# Motors.net
KiCad netlist of a schematic drawn in Altium Designer
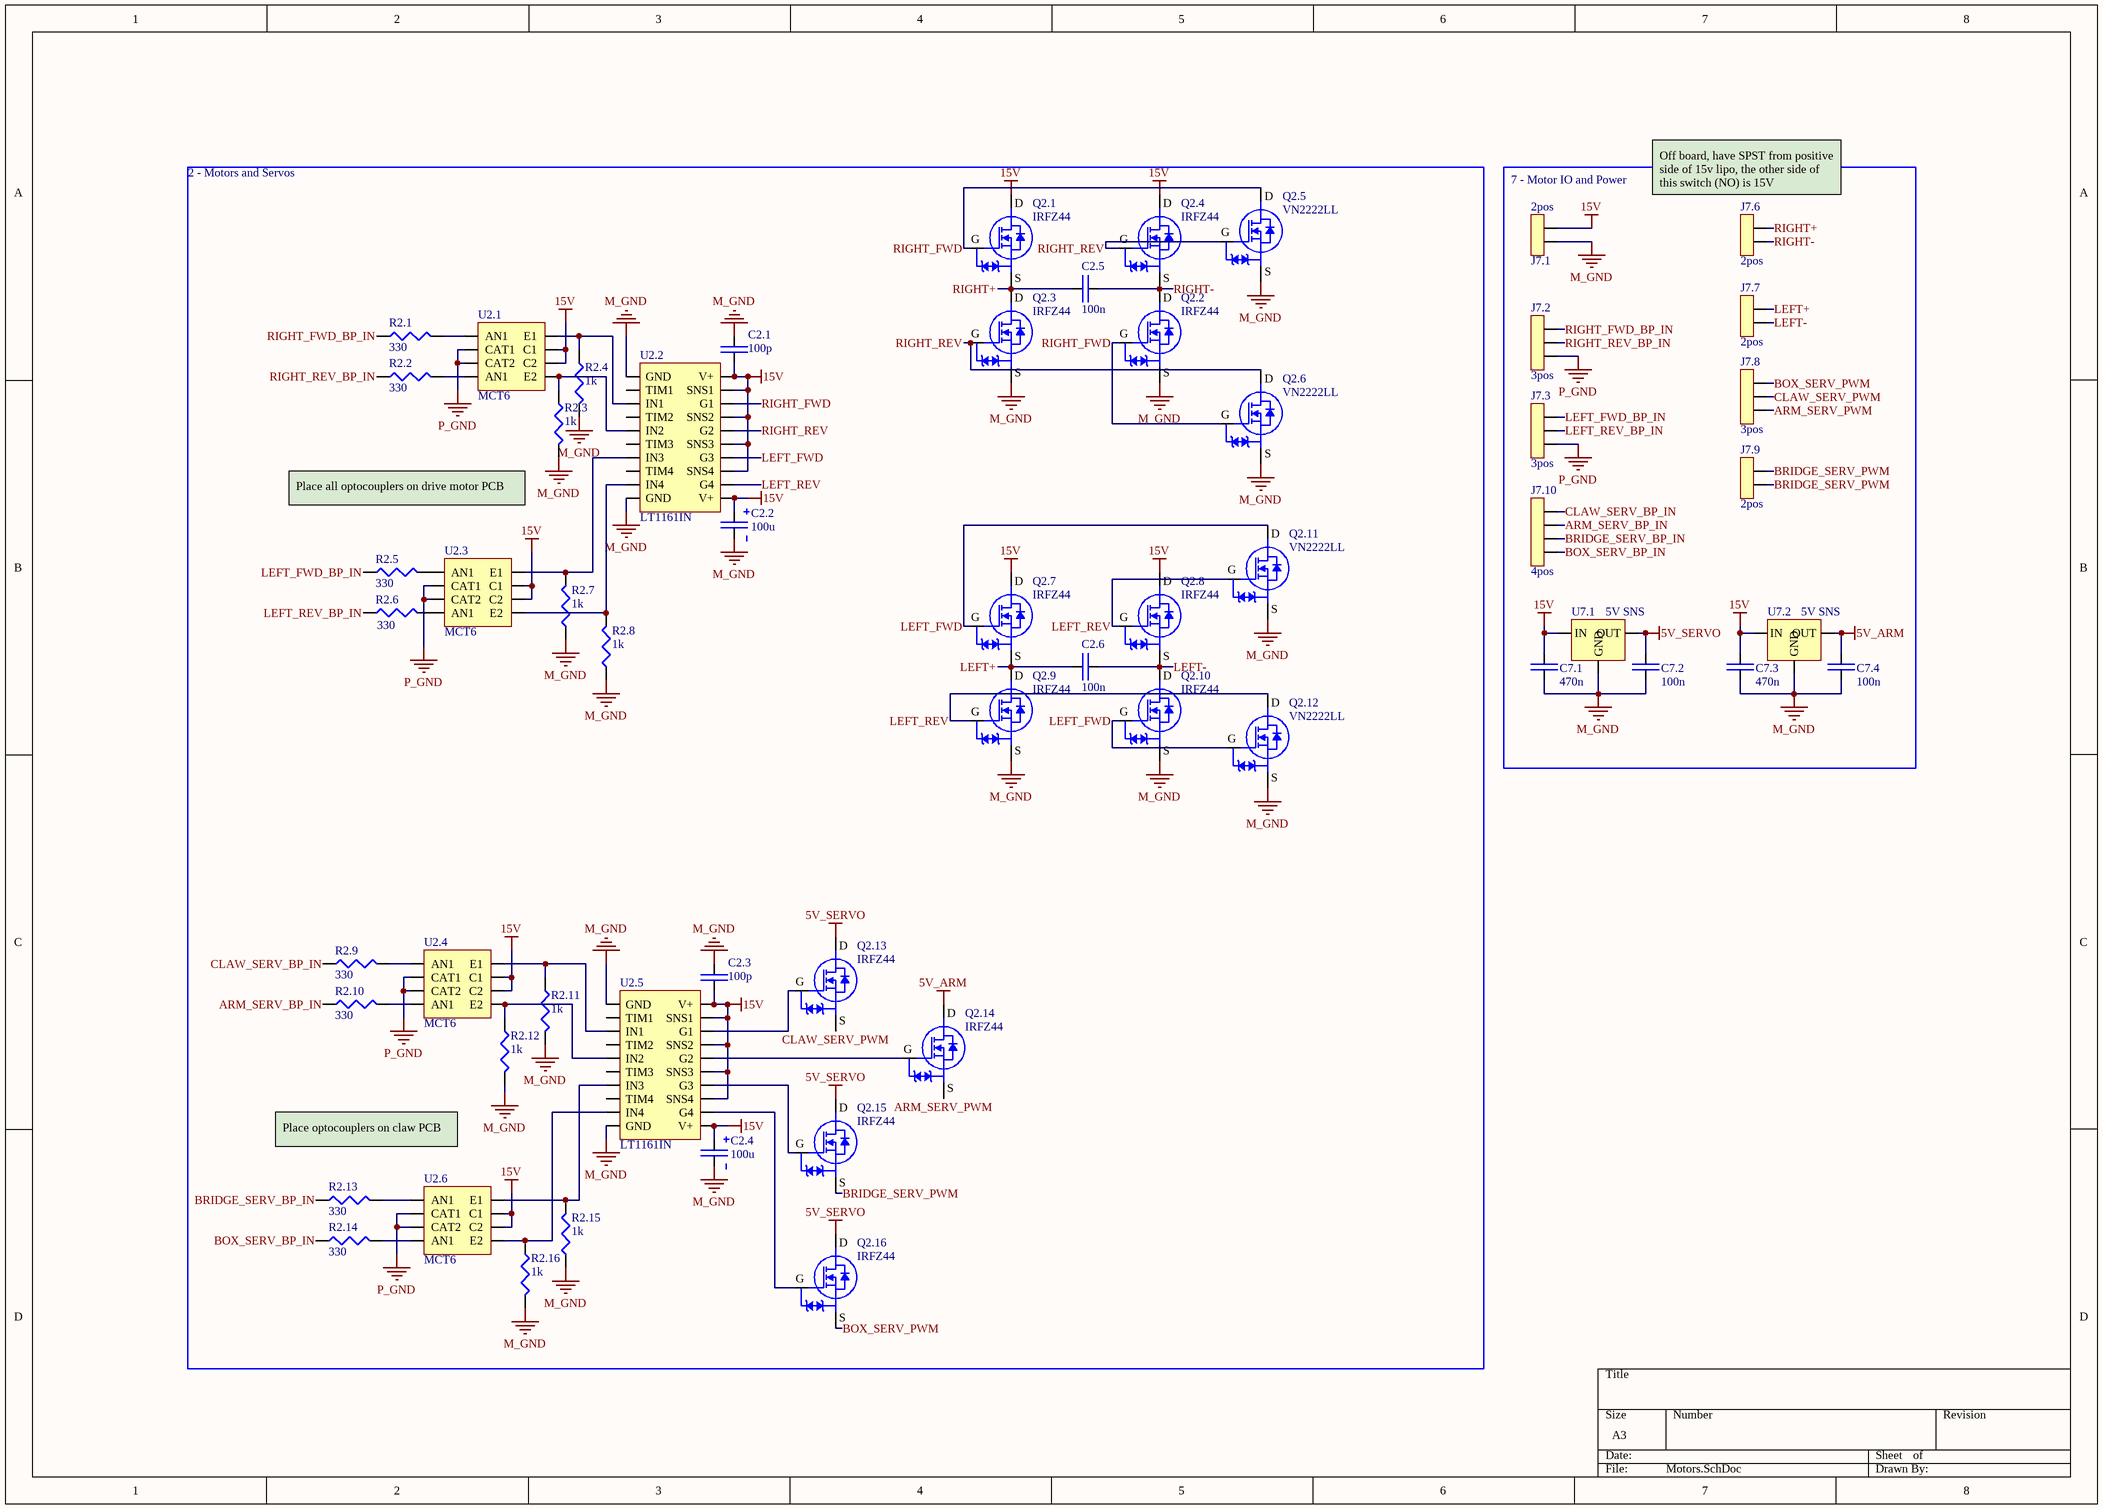
[diagram p0: Motors.SchDoc]

(export (version "E")
  (design (tool "Eeschema 10.0.6"))
  (components
    (comp (ref "C2.1")
      (value "100p")
      (footprint "Non Polarized Cap")
      (libsource (lib "SPICEBot_SchLib") (part "Cap_Generic"))
    )
    (comp (ref "C2.2")
      (value "100u")
      (footprint "Polarized Cap")
      (libsource (lib "SPICEBot_SchLib") (part "Polarized Cap"))
    )
    (comp (ref "C2.3")
      (value "100p")
      (footprint "Non Polarized Cap")
      (libsource (lib "SPICEBot_SchLib") (part "Cap_Generic"))
    )
    (comp (ref "C2.4")
      (value "100u")
      (footprint "Polarized Cap")
      (libsource (lib "SPICEBot_SchLib") (part "Polarized Cap"))
    )
    (comp (ref "C2.5")
      (value "100n")
      (footprint "Non Polarized Cap")
      (libsource (lib "SPICEBot_SchLib") (part "Cap_Generic"))
    )
    (comp (ref "C2.6")
      (value "100n")
      (footprint "Non Polarized Cap")
      (libsource (lib "SPICEBot_SchLib") (part "Cap_Generic"))
    )
    (comp (ref "C7.1")
      (value "470n")
      (footprint "Non Polarized Cap")
      (libsource (lib "SPICEBot_SchLib") (part "Cap_Generic"))
    )
    (comp (ref "C7.2")
      (value "100n")
      (footprint "Non Polarized Cap")
      (libsource (lib "SPICEBot_SchLib") (part "Cap_Generic"))
    )
    (comp (ref "C7.3")
      (value "470n")
      (footprint "Non Polarized Cap")
      (libsource (lib "SPICEBot_SchLib") (part "Cap_Generic"))
    )
    (comp (ref "C7.4")
      (value "100n")
      (footprint "Non Polarized Cap")
      (libsource (lib "SPICEBot_SchLib") (part "Cap_Generic"))
    )
    (comp (ref "J7.1")
      (value "2pos")
      (footprint "2pos JST")
      (description "2pos Conn JST")
      (libsource (lib "SPICEBot_SchLib") (part "2pos Conn"))
    )
    (comp (ref "J7.2")
      (value "3pos")
      (footprint "3pos JST")
      (description "3pos Conn")
      (libsource (lib "SPICEBot_SchLib") (part "3pos Conn"))
    )
    (comp (ref "J7.3")
      (value "3pos")
      (footprint "3pos JST")
      (description "3pos Conn")
      (libsource (lib "SPICEBot_SchLib") (part "3pos Conn"))
    )
    (comp (ref "J7.6")
      (value "2pos")
      (footprint "2pos JST")
      (description "2pos Conn JST")
      (libsource (lib "SPICEBot_SchLib") (part "2pos Conn"))
    )
    (comp (ref "J7.7")
      (value "2pos")
      (footprint "2pos JST")
      (description "2pos Conn JST")
      (libsource (lib "SPICEBot_SchLib") (part "2pos Conn"))
    )
    (comp (ref "J7.8")
      (value "3pos")
      (footprint "3pos JST")
      (description "3pos Conn")
      (libsource (lib "SPICEBot_SchLib") (part "3pos Conn"))
    )
    (comp (ref "J7.9")
      (value "2pos")
      (footprint "2pos JST")
      (description "2pos Conn JST")
      (libsource (lib "SPICEBot_SchLib") (part "2pos Conn"))
    )
    (comp (ref "J7.10")
      (value "4pos")
      (footprint "4Pos JST")
      (description "4pos Conn")
      (libsource (lib "SPICEBot_SchLib") (part "4pos Conn"))
    )
    (comp (ref "Q2.1")
      (value "IRFZ44")
      (footprint "TO220")
      (description "IRFZ44EPBF N-Channel 60 V 48A 110W Through Hole TO-220AB")
      (libsource (lib "SPICEBot_SchLib") (part "IRFZ44 NMOS"))
    )
    (comp (ref "Q2.2")
      (value "IRFZ44")
      (footprint "TO220")
      (description "IRFZ44EPBF N-Channel 60 V 48A 110W Through Hole TO-220AB")
      (libsource (lib "SPICEBot_SchLib") (part "IRFZ44 NMOS"))
    )
    (comp (ref "Q2.3")
      (value "IRFZ44")
      (footprint "TO220")
      (description "IRFZ44EPBF N-Channel 60 V 48A 110W Through Hole TO-220AB")
      (libsource (lib "SPICEBot_SchLib") (part "IRFZ44 NMOS"))
    )
    (comp (ref "Q2.4")
      (value "IRFZ44")
      (footprint "TO220")
      (description "IRFZ44EPBF N-Channel 60 V 48A 110W Through Hole TO-220AB")
      (libsource (lib "SPICEBot_SchLib") (part "IRFZ44 NMOS"))
    )
    (comp (ref "Q2.5")
      (value "VN2222LL")
      (footprint "VN2222LL")
      (description "VN2222LL N-Channel 60 V 150mA 400mW Through Hole TO-92 (TO-226)")
      (libsource (lib "SPICEBot_SchLib") (part "VN2222LL NMOS"))
    )
    (comp (ref "Q2.6")
      (value "VN2222LL")
      (footprint "VN2222LL")
      (description "VN2222LL N-Channel 60 V 150mA 400mW Through Hole TO-92 (TO-226)")
      (libsource (lib "SPICEBot_SchLib") (part "VN2222LL NMOS"))
    )
    (comp (ref "Q2.7")
      (value "IRFZ44")
      (footprint "TO220")
      (description "IRFZ44EPBF N-Channel 60 V 48A 110W Through Hole TO-220AB")
      (libsource (lib "SPICEBot_SchLib") (part "IRFZ44 NMOS"))
    )
    (comp (ref "Q2.8")
      (value "IRFZ44")
      (footprint "TO220")
      (description "IRFZ44EPBF N-Channel 60 V 48A 110W Through Hole TO-220AB")
      (libsource (lib "SPICEBot_SchLib") (part "IRFZ44 NMOS"))
    )
    (comp (ref "Q2.9")
      (value "IRFZ44")
      (footprint "TO220")
      (description "IRFZ44EPBF N-Channel 60 V 48A 110W Through Hole TO-220AB")
      (libsource (lib "SPICEBot_SchLib") (part "IRFZ44 NMOS"))
    )
    (comp (ref "Q2.10")
      (value "IRFZ44")
      (footprint "TO220")
      (description "IRFZ44EPBF N-Channel 60 V 48A 110W Through Hole TO-220AB")
      (libsource (lib "SPICEBot_SchLib") (part "IRFZ44 NMOS"))
    )
    (comp (ref "Q2.11")
      (value "VN2222LL")
      (footprint "VN2222LL")
      (description "VN2222LL N-Channel 60 V 150mA 400mW Through Hole TO-92 (TO-226)")
      (libsource (lib "SPICEBot_SchLib") (part "VN2222LL NMOS"))
    )
    (comp (ref "Q2.12")
      (value "VN2222LL")
      (footprint "VN2222LL")
      (description "VN2222LL N-Channel 60 V 150mA 400mW Through Hole TO-92 (TO-226)")
      (libsource (lib "SPICEBot_SchLib") (part "VN2222LL NMOS"))
    )
    (comp (ref "Q2.13")
      (value "IRFZ44")
      (footprint "TO220")
      (description "IRFZ44EPBF N-Channel 60 V 48A 110W Through Hole TO-220AB")
      (libsource (lib "SPICEBot_SchLib") (part "IRFZ44 NMOS"))
    )
    (comp (ref "Q2.14")
      (value "IRFZ44")
      (footprint "TO220")
      (description "IRFZ44EPBF N-Channel 60 V 48A 110W Through Hole TO-220AB")
      (libsource (lib "SPICEBot_SchLib") (part "IRFZ44 NMOS"))
    )
    (comp (ref "Q2.15")
      (value "IRFZ44")
      (footprint "TO220")
      (description "IRFZ44EPBF N-Channel 60 V 48A 110W Through Hole TO-220AB")
      (libsource (lib "SPICEBot_SchLib") (part "IRFZ44 NMOS"))
    )
    (comp (ref "Q2.16")
      (value "IRFZ44")
      (footprint "TO220")
      (description "IRFZ44EPBF N-Channel 60 V 48A 110W Through Hole TO-220AB")
      (libsource (lib "SPICEBot_SchLib") (part "IRFZ44 NMOS"))
    )
    (comp (ref "R2.1")
      (value "330")
      (footprint "Res_Generic")
      (libsource (lib "SPICEBot_SchLib") (part "Res_Generic"))
    )
    (comp (ref "R2.2")
      (value "330")
      (footprint "Res_Generic")
      (libsource (lib "SPICEBot_SchLib") (part "Res_Generic"))
    )
    (comp (ref "R2.3")
      (value "1k")
      (footprint "Res_Generic")
      (libsource (lib "SPICEBot_SchLib") (part "Res_Generic"))
    )
    (comp (ref "R2.4")
      (value "1k")
      (footprint "Res_Generic")
      (libsource (lib "SPICEBot_SchLib") (part "Res_Generic"))
    )
    (comp (ref "R2.5")
      (value "330")
      (footprint "Res_Generic")
      (libsource (lib "SPICEBot_SchLib") (part "Res_Generic"))
    )
    (comp (ref "R2.6")
      (value "330")
      (footprint "Res_Generic")
      (libsource (lib "SPICEBot_SchLib") (part "Res_Generic"))
    )
    (comp (ref "R2.7")
      (value "1k")
      (footprint "Res_Generic")
      (libsource (lib "SPICEBot_SchLib") (part "Res_Generic"))
    )
    (comp (ref "R2.8")
      (value "1k")
      (footprint "Res_Generic")
      (libsource (lib "SPICEBot_SchLib") (part "Res_Generic"))
    )
    (comp (ref "R2.9")
      (value "330")
      (footprint "Res_Generic")
      (libsource (lib "SPICEBot_SchLib") (part "Res_Generic"))
    )
    (comp (ref "R2.10")
      (value "330")
      (footprint "Res_Generic")
      (libsource (lib "SPICEBot_SchLib") (part "Res_Generic"))
    )
    (comp (ref "R2.11")
      (value "1k")
      (footprint "Res_Generic")
      (libsource (lib "SPICEBot_SchLib") (part "Res_Generic"))
    )
    (comp (ref "R2.12")
      (value "1k")
      (footprint "Res_Generic")
      (libsource (lib "SPICEBot_SchLib") (part "Res_Generic"))
    )
    (comp (ref "R2.13")
      (value "330")
      (footprint "Res_Generic")
      (libsource (lib "SPICEBot_SchLib") (part "Res_Generic"))
    )
    (comp (ref "R2.14")
      (value "330")
      (footprint "Res_Generic")
      (libsource (lib "SPICEBot_SchLib") (part "Res_Generic"))
    )
    (comp (ref "R2.15")
      (value "1k")
      (footprint "Res_Generic")
      (libsource (lib "SPICEBot_SchLib") (part "Res_Generic"))
    )
    (comp (ref "R2.16")
      (value "1k")
      (footprint "Res_Generic")
      (libsource (lib "SPICEBot_SchLib") (part "Res_Generic"))
    )
    (comp (ref "U2.1")
      (value "MCT6")
      (footprint "DIP8")
      (description "Optoisolator 5.3KV 2CH TRANS 8-DIP")
      (libsource (lib "SPICEBot_SchLib") (part "MCT6 Optocoupler"))
    )
    (comp (ref "U2.2")
      (value "LT1161IN")
      (footprint "DIP20")
      (description "LT1161IN High-Side Gate Driver IC Non-Inverting 20-PDIP")
      (libsource (lib "SPICEBot_SchLib") (part "LT1161IN Gate Driver"))
    )
    (comp (ref "U2.3")
      (value "MCT6")
      (footprint "DIP8")
      (description "Optoisolator 5.3KV 2CH TRANS 8-DIP")
      (libsource (lib "SPICEBot_SchLib") (part "MCT6 Optocoupler"))
    )
    (comp (ref "U2.4")
      (value "MCT6")
      (footprint "DIP8")
      (description "Optoisolator 5.3KV 2CH TRANS 8-DIP")
      (libsource (lib "SPICEBot_SchLib") (part "MCT6 Optocoupler"))
    )
    (comp (ref "U2.5")
      (value "LT1161IN")
      (footprint "DIP20")
      (description "LT1161IN High-Side Gate Driver IC Non-Inverting 20-PDIP")
      (libsource (lib "SPICEBot_SchLib") (part "LT1161IN Gate Driver"))
    )
    (comp (ref "U2.6")
      (value "MCT6")
      (footprint "DIP8")
      (description "Optoisolator 5.3KV 2CH TRANS 8-DIP")
      (libsource (lib "SPICEBot_SchLib") (part "MCT6 Optocoupler"))
    )
    (comp (ref "U7.1")
      (value "5V SNS")
      (footprint "TO220")
      (description "UA7805 IC REG LINEAR 5V 1.5A TO220-3")
      (libsource (lib "SPICEBot_SchLib") (part "UA7805 5V Reg"))
    )
    (comp (ref "U7.2")
      (value "5V SNS")
      (footprint "TO220")
      (description "UA7805 IC REG LINEAR 5V 1.5A TO220-3")
      (libsource (lib "SPICEBot_SchLib") (part "UA7805 5V Reg"))
    )
  )
  (nets
    (net (code "1") (name "/ARM_SERV_BP_IN") (class "Default")
      (node (ref "J7.10") (pin "3") (pinfunction "3_3") (pintype "passive"))
      (node (ref "R2.10") (pin "1") (pinfunction "1_1") (pintype "passive"))
    )
    (net (code "2") (name "/ARM_SERV_PWM") (class "Default")
      (node (ref "J7.8") (pin "1") (pinfunction "1_1") (pintype "passive"))
      (node (ref "Q2.14") (pin "2") (pinfunction "S_2") (pintype "passive"))
    )
    (net (code "3") (name "/BOX_SERV_BP_IN") (class "Default")
      (node (ref "J7.10") (pin "1") (pinfunction "1_1") (pintype "passive"))
      (node (ref "R2.14") (pin "1") (pinfunction "1_1") (pintype "passive"))
    )
    (net (code "4") (name "/BOX_SERV_PWM") (class "Default")
      (node (ref "J7.8") (pin "3") (pinfunction "3_3") (pintype "passive"))
      (node (ref "Q2.16") (pin "2") (pinfunction "S_2") (pintype "passive"))
    )
    (net (code "5") (name "/BRIDGE_SERV_BP_IN") (class "Default")
      (node (ref "J7.10") (pin "2") (pinfunction "2_2") (pintype "passive"))
      (node (ref "R2.13") (pin "1") (pinfunction "1_1") (pintype "passive"))
    )
    (net (code "6") (name "/BRIDGE_SERV_PWM") (class "Default")
      (node (ref "J7.9") (pin "1") (pinfunction "1_1") (pintype "passive"))
      (node (ref "J7.9") (pin "2") (pinfunction "2_2") (pintype "passive"))
      (node (ref "Q2.15") (pin "2") (pinfunction "S_2") (pintype "passive"))
    )
    (net (code "7") (name "/CLAW_SERV_BP_IN") (class "Default")
      (node (ref "J7.10") (pin "4") (pinfunction "4_4") (pintype "passive"))
      (node (ref "R2.9") (pin "1") (pinfunction "1_1") (pintype "passive"))
    )
    (net (code "8") (name "/CLAW_SERV_PWM") (class "Default")
      (node (ref "J7.8") (pin "2") (pinfunction "2_2") (pintype "passive"))
      (node (ref "Q2.13") (pin "2") (pinfunction "S_2") (pintype "passive"))
    )
    (net (code "9") (name "/LEFT+") (class "Default")
      (node (ref "C2.6") (pin "1") (pinfunction "1_1") (pintype "passive"))
      (node (ref "J7.7") (pin "2") (pinfunction "2_2") (pintype "passive"))
      (node (ref "Q2.7") (pin "2") (pinfunction "S_2") (pintype "passive"))
      (node (ref "Q2.9") (pin "3") (pinfunction "D_3") (pintype "passive"))
    )
    (net (code "10") (name "/LEFT-") (class "Default")
      (node (ref "C2.6") (pin "2") (pinfunction "2_2") (pintype "passive"))
      (node (ref "J7.7") (pin "1") (pinfunction "1_1") (pintype "passive"))
      (node (ref "Q2.10") (pin "3") (pinfunction "D_3") (pintype "passive"))
      (node (ref "Q2.8") (pin "2") (pinfunction "S_2") (pintype "passive"))
    )
    (net (code "11") (name "/LEFT_FWD") (class "Default")
      (node (ref "Q2.10") (pin "1") (pinfunction "G_1") (pintype "passive"))
      (node (ref "Q2.11") (pin "3") (pinfunction "D_3") (pintype "passive"))
      (node (ref "Q2.12") (pin "1") (pinfunction "G_1") (pintype "passive"))
      (node (ref "Q2.7") (pin "1") (pinfunction "G_1") (pintype "passive"))
      (node (ref "U2.2") (pin "14") (pinfunction "G3_14") (pintype "passive"))
    )
    (net (code "12") (name "/LEFT_FWD_BP_IN") (class "Default")
      (node (ref "J7.3") (pin "3") (pinfunction "3_3") (pintype "passive"))
      (node (ref "R2.5") (pin "1") (pinfunction "1_1") (pintype "passive"))
    )
    (net (code "13") (name "/LEFT_REV") (class "Default")
      (node (ref "Q2.11") (pin "1") (pinfunction "G_1") (pintype "passive"))
      (node (ref "Q2.12") (pin "3") (pinfunction "D_3") (pintype "passive"))
      (node (ref "Q2.8") (pin "1") (pinfunction "G_1") (pintype "passive"))
      (node (ref "Q2.9") (pin "1") (pinfunction "G_1") (pintype "passive"))
      (node (ref "U2.2") (pin "12") (pinfunction "G4_12") (pintype "passive"))
    )
    (net (code "14") (name "/LEFT_REV_BP_IN") (class "Default")
      (node (ref "J7.3") (pin "2") (pinfunction "2_2") (pintype "passive"))
      (node (ref "R2.6") (pin "1") (pinfunction "1_1") (pintype "passive"))
    )
    (net (code "15") (name "/RIGHT+") (class "Default")
      (node (ref "C2.5") (pin "1") (pinfunction "1_1") (pintype "passive"))
      (node (ref "J7.6") (pin "2") (pinfunction "2_2") (pintype "passive"))
      (node (ref "Q2.1") (pin "2") (pinfunction "S_2") (pintype "passive"))
      (node (ref "Q2.3") (pin "3") (pinfunction "D_3") (pintype "passive"))
    )
    (net (code "16") (name "/RIGHT-") (class "Default")
      (node (ref "C2.5") (pin "2") (pinfunction "2_2") (pintype "passive"))
      (node (ref "J7.6") (pin "1") (pinfunction "1_1") (pintype "passive"))
      (node (ref "Q2.2") (pin "3") (pinfunction "D_3") (pintype "passive"))
      (node (ref "Q2.4") (pin "2") (pinfunction "S_2") (pintype "passive"))
    )
    (net (code "17") (name "/RIGHT_FWD") (class "Default")
      (node (ref "Q2.1") (pin "1") (pinfunction "G_1") (pintype "passive"))
      (node (ref "Q2.2") (pin "1") (pinfunction "G_1") (pintype "passive"))
      (node (ref "Q2.5") (pin "3") (pinfunction "D_3") (pintype "passive"))
      (node (ref "Q2.6") (pin "1") (pinfunction "G_1") (pintype "passive"))
      (node (ref "U2.2") (pin "18") (pinfunction "G1_18") (pintype "passive"))
    )
    (net (code "18") (name "/RIGHT_FWD_BP_IN") (class "Default")
      (node (ref "J7.2") (pin "3") (pinfunction "3_3") (pintype "passive"))
      (node (ref "R2.1") (pin "1") (pinfunction "1_1") (pintype "passive"))
    )
    (net (code "19") (name "/RIGHT_REV") (class "Default")
      (node (ref "Q2.3") (pin "1") (pinfunction "G_1") (pintype "passive"))
      (node (ref "Q2.4") (pin "1") (pinfunction "G_1") (pintype "passive"))
      (node (ref "Q2.5") (pin "1") (pinfunction "G_1") (pintype "passive"))
      (node (ref "Q2.6") (pin "3") (pinfunction "D_3") (pintype "passive"))
      (node (ref "U2.2") (pin "16") (pinfunction "G2_16") (pintype "passive"))
    )
    (net (code "20") (name "/RIGHT_REV_BP_IN") (class "Default")
      (node (ref "J7.2") (pin "2") (pinfunction "2_2") (pintype "passive"))
      (node (ref "R2.2") (pin "1") (pinfunction "1_1") (pintype "passive"))
    )
    (net (code "21") (name "5V_ARM") (class "Default")
      (node (ref "C7.4") (pin "2") (pinfunction "2_2") (pintype "passive"))
      (node (ref "Q2.14") (pin "3") (pinfunction "D_3") (pintype "passive"))
      (node (ref "U7.2") (pin "3") (pinfunction "OUT_3") (pintype "passive"))
    )
    (net (code "22") (name "5V_SERVO") (class "Default")
      (node (ref "C7.2") (pin "2") (pinfunction "2_2") (pintype "passive"))
      (node (ref "Q2.13") (pin "3") (pinfunction "D_3") (pintype "passive"))
      (node (ref "Q2.15") (pin "3") (pinfunction "D_3") (pintype "passive"))
      (node (ref "Q2.16") (pin "3") (pinfunction "D_3") (pintype "passive"))
      (node (ref "U7.1") (pin "3") (pinfunction "OUT_3") (pintype "passive"))
    )
    (net (code "23") (name "15V") (class "Default")
      (node (ref "C2.1") (pin "1") (pinfunction "1_1") (pintype "passive"))
      (node (ref "C2.2") (pin "1") (pinfunction "1_1") (pintype "passive"))
      (node (ref "C2.3") (pin "1") (pinfunction "1_1") (pintype "passive"))
      (node (ref "C2.4") (pin "1") (pinfunction "1_1") (pintype "passive"))
      (node (ref "C7.1") (pin "2") (pinfunction "2_2") (pintype "passive"))
      (node (ref "C7.3") (pin "2") (pinfunction "2_2") (pintype "passive"))
      (node (ref "J7.1") (pin "2") (pinfunction "2_2") (pintype "passive"))
      (node (ref "Q2.1") (pin "3") (pinfunction "D_3") (pintype "passive"))
      (node (ref "Q2.4") (pin "3") (pinfunction "D_3") (pintype "passive"))
      (node (ref "Q2.7") (pin "3") (pinfunction "D_3") (pintype "passive"))
      (node (ref "Q2.8") (pin "3") (pinfunction "D_3") (pintype "passive"))
      (node (ref "U2.1") (pin "6") (pinfunction "C2_6") (pintype "passive"))
      (node (ref "U2.1") (pin "7") (pinfunction "C1_7") (pintype "passive"))
      (node (ref "U2.2") (pin "11") (pinfunction "V+_11") (pintype "passive"))
      (node (ref "U2.2") (pin "13") (pinfunction "SNS4_13") (pintype "passive"))
      (node (ref "U2.2") (pin "15") (pinfunction "SNS3_15") (pintype "passive"))
      (node (ref "U2.2") (pin "17") (pinfunction "SNS2_17") (pintype "passive"))
      (node (ref "U2.2") (pin "19") (pinfunction "SNS1_19") (pintype "passive"))
      (node (ref "U2.2") (pin "20") (pinfunction "V+_20") (pintype "passive"))
      (node (ref "U2.3") (pin "6") (pinfunction "C2_6") (pintype "passive"))
      (node (ref "U2.3") (pin "7") (pinfunction "C1_7") (pintype "passive"))
      (node (ref "U2.4") (pin "6") (pinfunction "C2_6") (pintype "passive"))
      (node (ref "U2.4") (pin "7") (pinfunction "C1_7") (pintype "passive"))
      (node (ref "U2.5") (pin "11") (pinfunction "V+_11") (pintype "passive"))
      (node (ref "U2.5") (pin "13") (pinfunction "SNS4_13") (pintype "passive"))
      (node (ref "U2.5") (pin "15") (pinfunction "SNS3_15") (pintype "passive"))
      (node (ref "U2.5") (pin "17") (pinfunction "SNS2_17") (pintype "passive"))
      (node (ref "U2.5") (pin "19") (pinfunction "SNS1_19") (pintype "passive"))
      (node (ref "U2.5") (pin "20") (pinfunction "V+_20") (pintype "passive"))
      (node (ref "U2.6") (pin "6") (pinfunction "C2_6") (pintype "passive"))
      (node (ref "U2.6") (pin "7") (pinfunction "C1_7") (pintype "passive"))
      (node (ref "U7.1") (pin "1") (pinfunction "IN_1") (pintype "passive"))
      (node (ref "U7.2") (pin "1") (pinfunction "IN_1") (pintype "passive"))
    )
    (net (code "24") (name "M_GND") (class "Default")
      (node (ref "C2.1") (pin "2") (pinfunction "2_2") (pintype "passive"))
      (node (ref "C2.2") (pin "2") (pinfunction "2_2") (pintype "passive"))
      (node (ref "C2.3") (pin "2") (pinfunction "2_2") (pintype "passive"))
      (node (ref "C2.4") (pin "2") (pinfunction "2_2") (pintype "passive"))
      (node (ref "C7.1") (pin "1") (pinfunction "1_1") (pintype "passive"))
      (node (ref "C7.2") (pin "1") (pinfunction "1_1") (pintype "passive"))
      (node (ref "C7.3") (pin "1") (pinfunction "1_1") (pintype "passive"))
      (node (ref "C7.4") (pin "1") (pinfunction "1_1") (pintype "passive"))
      (node (ref "J7.1") (pin "1") (pinfunction "1_1") (pintype "passive"))
      (node (ref "Q2.10") (pin "2") (pinfunction "S_2") (pintype "passive"))
      (node (ref "Q2.11") (pin "2") (pinfunction "S_2") (pintype "passive"))
      (node (ref "Q2.12") (pin "2") (pinfunction "S_2") (pintype "passive"))
      (node (ref "Q2.2") (pin "2") (pinfunction "S_2") (pintype "passive"))
      (node (ref "Q2.3") (pin "2") (pinfunction "S_2") (pintype "passive"))
      (node (ref "Q2.5") (pin "2") (pinfunction "S_2") (pintype "passive"))
      (node (ref "Q2.6") (pin "2") (pinfunction "S_2") (pintype "passive"))
      (node (ref "Q2.9") (pin "2") (pinfunction "S_2") (pintype "passive"))
      (node (ref "R2.11") (pin "2") (pinfunction "2_2") (pintype "passive"))
      (node (ref "R2.12") (pin "2") (pinfunction "2_2") (pintype "passive"))
      (node (ref "R2.15") (pin "1") (pinfunction "1_1") (pintype "passive"))
      (node (ref "R2.16") (pin "2") (pinfunction "2_2") (pintype "passive"))
      (node (ref "R2.3") (pin "2") (pinfunction "2_2") (pintype "passive"))
      (node (ref "R2.4") (pin "2") (pinfunction "2_2") (pintype "passive"))
      (node (ref "R2.7") (pin "1") (pinfunction "1_1") (pintype "passive"))
      (node (ref "R2.8") (pin "1") (pinfunction "1_1") (pintype "passive"))
      (node (ref "U2.2") (pin "1") (pinfunction "GND_1") (pintype "passive"))
      (node (ref "U2.2") (pin "10") (pinfunction "GND_10") (pintype "passive"))
      (node (ref "U2.5") (pin "1") (pinfunction "GND_1") (pintype "passive"))
      (node (ref "U2.5") (pin "10") (pinfunction "GND_10") (pintype "passive"))
      (node (ref "U7.1") (pin "2") (pinfunction "GND_2") (pintype "passive"))
      (node (ref "U7.2") (pin "2") (pinfunction "GND_2") (pintype "passive"))
    )
    (net (code "25") (name "Net-(Q2.13-G)") (class "Default")
      (node (ref "Q2.13") (pin "1") (pinfunction "G_1") (pintype "passive"))
      (node (ref "U2.5") (pin "18") (pinfunction "G1_18") (pintype "passive"))
    )
    (net (code "26") (name "Net-(Q2.14-G)") (class "Default")
      (node (ref "Q2.14") (pin "1") (pinfunction "G_1") (pintype "passive"))
      (node (ref "U2.5") (pin "16") (pinfunction "G2_16") (pintype "passive"))
    )
    (net (code "27") (name "Net-(Q2.15-G)") (class "Default")
      (node (ref "Q2.15") (pin "1") (pinfunction "G_1") (pintype "passive"))
      (node (ref "U2.5") (pin "14") (pinfunction "G3_14") (pintype "passive"))
    )
    (net (code "28") (name "Net-(Q2.16-G)") (class "Default")
      (node (ref "Q2.16") (pin "1") (pinfunction "G_1") (pintype "passive"))
      (node (ref "U2.5") (pin "12") (pinfunction "G4_12") (pintype "passive"))
    )
    (net (code "29") (name "Net-(R2.1-Pad2)") (class "Default")
      (node (ref "R2.1") (pin "2") (pinfunction "2_2") (pintype "passive"))
      (node (ref "U2.1") (pin "1") (pinfunction "AN1_1") (pintype "passive"))
    )
    (net (code "30") (name "Net-(R2.2-Pad2)") (class "Default")
      (node (ref "R2.2") (pin "2") (pinfunction "2_2") (pintype "passive"))
      (node (ref "U2.1") (pin "4") (pinfunction "AN1_4") (pintype "passive"))
    )
    (net (code "31") (name "Net-(R2.5-Pad2)") (class "Default")
      (node (ref "R2.5") (pin "2") (pinfunction "2_2") (pintype "passive"))
      (node (ref "U2.3") (pin "1") (pinfunction "AN1_1") (pintype "passive"))
    )
    (net (code "32") (name "Net-(R2.6-Pad2)") (class "Default")
      (node (ref "R2.6") (pin "2") (pinfunction "2_2") (pintype "passive"))
      (node (ref "U2.3") (pin "4") (pinfunction "AN1_4") (pintype "passive"))
    )
    (net (code "33") (name "Net-(R2.9-Pad2)") (class "Default")
      (node (ref "R2.9") (pin "2") (pinfunction "2_2") (pintype "passive"))
      (node (ref "U2.4") (pin "1") (pinfunction "AN1_1") (pintype "passive"))
    )
    (net (code "34") (name "Net-(R2.10-Pad2)") (class "Default")
      (node (ref "R2.10") (pin "2") (pinfunction "2_2") (pintype "passive"))
      (node (ref "U2.4") (pin "4") (pinfunction "AN1_4") (pintype "passive"))
    )
    (net (code "35") (name "Net-(R2.13-Pad2)") (class "Default")
      (node (ref "R2.13") (pin "2") (pinfunction "2_2") (pintype "passive"))
      (node (ref "U2.6") (pin "1") (pinfunction "AN1_1") (pintype "passive"))
    )
    (net (code "36") (name "Net-(R2.14-Pad2)") (class "Default")
      (node (ref "R2.14") (pin "2") (pinfunction "2_2") (pintype "passive"))
      (node (ref "U2.6") (pin "4") (pinfunction "AN1_4") (pintype "passive"))
    )
    (net (code "37") (name "Net-(U2.1-E1)") (class "Default")
      (node (ref "R2.4") (pin "1") (pinfunction "1_1") (pintype "passive"))
      (node (ref "U2.1") (pin "8") (pinfunction "E1_8") (pintype "passive"))
      (node (ref "U2.2") (pin "3") (pinfunction "IN1_3") (pintype "passive"))
    )
    (net (code "38") (name "Net-(U2.1-E2)") (class "Default")
      (node (ref "R2.3") (pin "1") (pinfunction "1_1") (pintype "passive"))
      (node (ref "U2.1") (pin "5") (pinfunction "E2_5") (pintype "passive"))
      (node (ref "U2.2") (pin "5") (pinfunction "IN2_5") (pintype "passive"))
    )
    (net (code "39") (name "Net-(U2.2-IN3)") (class "Default")
      (node (ref "R2.7") (pin "2") (pinfunction "2_2") (pintype "passive"))
      (node (ref "U2.2") (pin "7") (pinfunction "IN3_7") (pintype "passive"))
      (node (ref "U2.3") (pin "8") (pinfunction "E1_8") (pintype "passive"))
    )
    (net (code "40") (name "Net-(U2.2-IN4)") (class "Default")
      (node (ref "R2.8") (pin "2") (pinfunction "2_2") (pintype "passive"))
      (node (ref "U2.2") (pin "9") (pinfunction "IN4_9") (pintype "passive"))
      (node (ref "U2.3") (pin "5") (pinfunction "E2_5") (pintype "passive"))
    )
    (net (code "41") (name "Net-(U2.4-E1)") (class "Default")
      (node (ref "R2.11") (pin "1") (pinfunction "1_1") (pintype "passive"))
      (node (ref "U2.4") (pin "8") (pinfunction "E1_8") (pintype "passive"))
      (node (ref "U2.5") (pin "3") (pinfunction "IN1_3") (pintype "passive"))
    )
    (net (code "42") (name "Net-(U2.4-E2)") (class "Default")
      (node (ref "R2.12") (pin "1") (pinfunction "1_1") (pintype "passive"))
      (node (ref "U2.4") (pin "5") (pinfunction "E2_5") (pintype "passive"))
      (node (ref "U2.5") (pin "5") (pinfunction "IN2_5") (pintype "passive"))
    )
    (net (code "43") (name "Net-(U2.5-IN3)") (class "Default")
      (node (ref "R2.15") (pin "2") (pinfunction "2_2") (pintype "passive"))
      (node (ref "U2.5") (pin "7") (pinfunction "IN3_7") (pintype "passive"))
      (node (ref "U2.6") (pin "8") (pinfunction "E1_8") (pintype "passive"))
    )
    (net (code "44") (name "Net-(U2.5-IN4)") (class "Default")
      (node (ref "R2.16") (pin "1") (pinfunction "1_1") (pintype "passive"))
      (node (ref "U2.5") (pin "9") (pinfunction "IN4_9") (pintype "passive"))
      (node (ref "U2.6") (pin "5") (pinfunction "E2_5") (pintype "passive"))
    )
    (net (code "45") (name "P_GND") (class "Default")
      (node (ref "J7.2") (pin "1") (pinfunction "1_1") (pintype "passive"))
      (node (ref "J7.3") (pin "1") (pinfunction "1_1") (pintype "passive"))
      (node (ref "U2.1") (pin "2") (pinfunction "CAT1_2") (pintype "passive"))
      (node (ref "U2.1") (pin "3") (pinfunction "CAT2_3") (pintype "passive"))
      (node (ref "U2.3") (pin "2") (pinfunction "CAT1_2") (pintype "passive"))
      (node (ref "U2.3") (pin "3") (pinfunction "CAT2_3") (pintype "passive"))
      (node (ref "U2.4") (pin "2") (pinfunction "CAT1_2") (pintype "passive"))
      (node (ref "U2.4") (pin "3") (pinfunction "CAT2_3") (pintype "passive"))
      (node (ref "U2.6") (pin "2") (pinfunction "CAT1_2") (pintype "passive"))
      (node (ref "U2.6") (pin "3") (pinfunction "CAT2_3") (pintype "passive"))
    )
    (net (code "46") (name "unconnected-(U2.2-TIM1-Pad2)") (class "Default")
      (node (ref "U2.2") (pin "2") (pinfunction "TIM1_2") (pintype "passive"))
    )
    (net (code "47") (name "unconnected-(U2.2-TIM2-Pad4)") (class "Default")
      (node (ref "U2.2") (pin "4") (pinfunction "TIM2_4") (pintype "passive"))
    )
    (net (code "48") (name "unconnected-(U2.2-TIM3-Pad6)") (class "Default")
      (node (ref "U2.2") (pin "6") (pinfunction "TIM3_6") (pintype "passive"))
    )
    (net (code "49") (name "unconnected-(U2.2-TIM4-Pad8)") (class "Default")
      (node (ref "U2.2") (pin "8") (pinfunction "TIM4_8") (pintype "passive"))
    )
    (net (code "50") (name "unconnected-(U2.5-TIM1-Pad2)") (class "Default")
      (node (ref "U2.5") (pin "2") (pinfunction "TIM1_2") (pintype "passive"))
    )
    (net (code "51") (name "unconnected-(U2.5-TIM2-Pad4)") (class "Default")
      (node (ref "U2.5") (pin "4") (pinfunction "TIM2_4") (pintype "passive"))
    )
    (net (code "52") (name "unconnected-(U2.5-TIM3-Pad6)") (class "Default")
      (node (ref "U2.5") (pin "6") (pinfunction "TIM3_6") (pintype "passive"))
    )
    (net (code "53") (name "unconnected-(U2.5-TIM4-Pad8)") (class "Default")
      (node (ref "U2.5") (pin "8") (pinfunction "TIM4_8") (pintype "passive"))
    )
  )
)
